# DMD_1_0.net
KiCad netlist of a schematic drawn in EAGLE
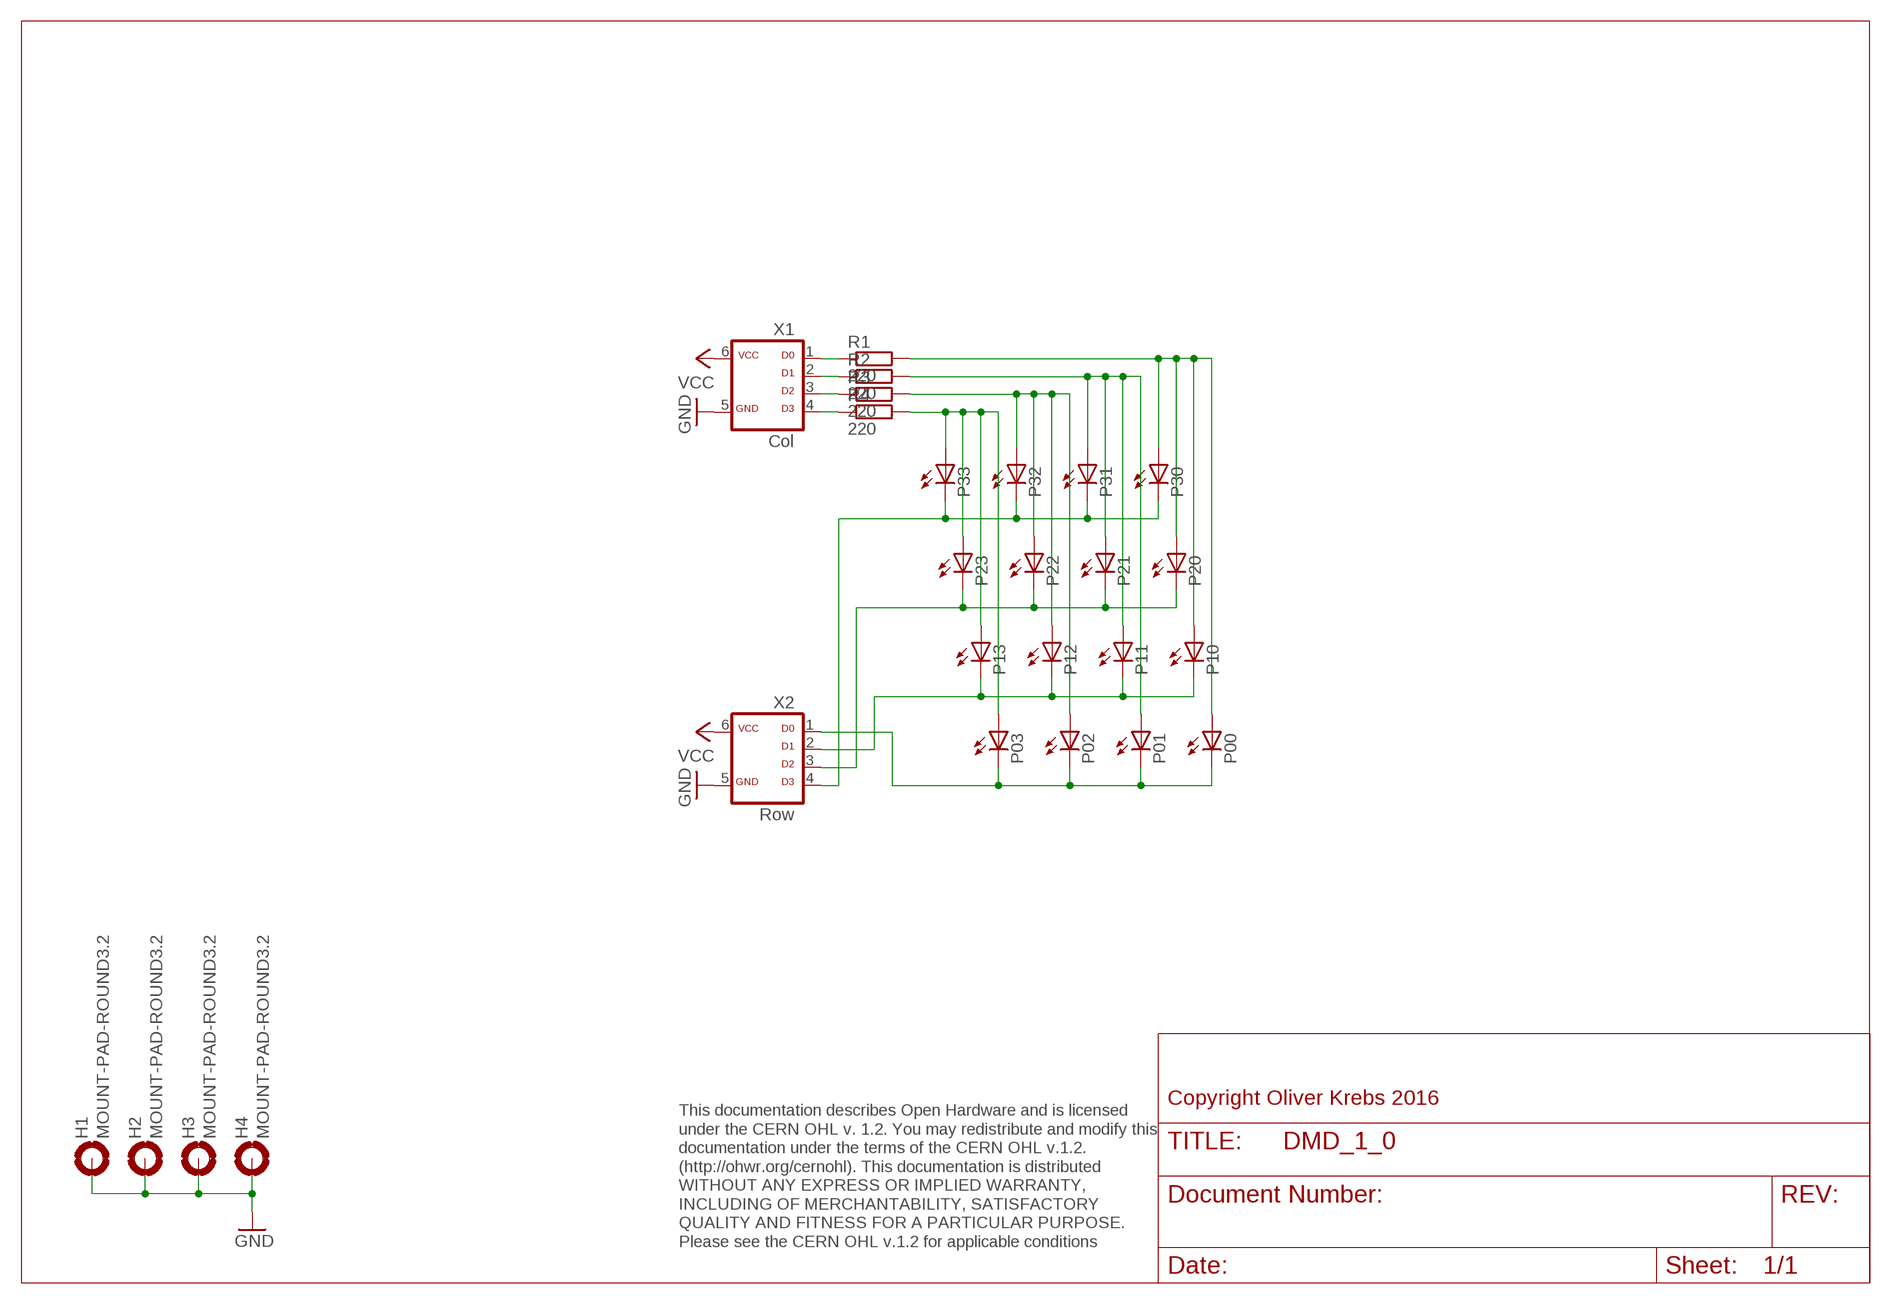
[diagram p0: schematic, sheet 1]

(export (version "E")
  (design (tool "Eeschema 10.0.6"))
  (components
    (comp (ref "H1")
      (value "MOUNT-PAD-ROUND3.2")
      (footprint "eagle-import:3,2-PAD")
      (libsource (lib "eagle-import") (part "MOUNT-PAD-ROUND3.2"))
    )
    (comp (ref "H2")
      (value "MOUNT-PAD-ROUND3.2")
      (footprint "eagle-import:3,2-PAD")
      (libsource (lib "eagle-import") (part "MOUNT-PAD-ROUND3.2"))
    )
    (comp (ref "H3")
      (value "MOUNT-PAD-ROUND3.2")
      (footprint "eagle-import:3,2-PAD")
      (libsource (lib "eagle-import") (part "MOUNT-PAD-ROUND3.2"))
    )
    (comp (ref "H4")
      (value "MOUNT-PAD-ROUND3.2")
      (footprint "eagle-import:3,2-PAD")
      (libsource (lib "eagle-import") (part "MOUNT-PAD-ROUND3.2"))
    )
    (comp (ref "P00")
      (value "LED5MM")
      (footprint "eagle-import:LED5MM")
      (libsource (lib "eagle-import") (part "LED5MM"))
    )
    (comp (ref "P01")
      (value "LED5MM")
      (footprint "eagle-import:LED5MM")
      (libsource (lib "eagle-import") (part "LED5MM"))
    )
    (comp (ref "P02")
      (value "LED5MM")
      (footprint "eagle-import:LED5MM")
      (libsource (lib "eagle-import") (part "LED5MM"))
    )
    (comp (ref "P03")
      (value "LED5MM")
      (footprint "eagle-import:LED5MM")
      (libsource (lib "eagle-import") (part "LED5MM"))
    )
    (comp (ref "P10")
      (value "LED5MM")
      (footprint "eagle-import:LED5MM")
      (libsource (lib "eagle-import") (part "LED5MM"))
    )
    (comp (ref "P11")
      (value "LED5MM")
      (footprint "eagle-import:LED5MM")
      (libsource (lib "eagle-import") (part "LED5MM"))
    )
    (comp (ref "P12")
      (value "LED5MM")
      (footprint "eagle-import:LED5MM")
      (libsource (lib "eagle-import") (part "LED5MM"))
    )
    (comp (ref "P13")
      (value "LED5MM")
      (footprint "eagle-import:LED5MM")
      (libsource (lib "eagle-import") (part "LED5MM"))
    )
    (comp (ref "P20")
      (value "LED5MM")
      (footprint "eagle-import:LED5MM")
      (libsource (lib "eagle-import") (part "LED5MM"))
    )
    (comp (ref "P21")
      (value "LED5MM")
      (footprint "eagle-import:LED5MM")
      (libsource (lib "eagle-import") (part "LED5MM"))
    )
    (comp (ref "P22")
      (value "LED5MM")
      (footprint "eagle-import:LED5MM")
      (libsource (lib "eagle-import") (part "LED5MM"))
    )
    (comp (ref "P23")
      (value "LED5MM")
      (footprint "eagle-import:LED5MM")
      (libsource (lib "eagle-import") (part "LED5MM"))
    )
    (comp (ref "P30")
      (value "LED5MM")
      (footprint "eagle-import:LED5MM")
      (libsource (lib "eagle-import") (part "LED5MM"))
    )
    (comp (ref "P31")
      (value "LED5MM")
      (footprint "eagle-import:LED5MM")
      (libsource (lib "eagle-import") (part "LED5MM"))
    )
    (comp (ref "P32")
      (value "LED5MM")
      (footprint "eagle-import:LED5MM")
      (libsource (lib "eagle-import") (part "LED5MM"))
    )
    (comp (ref "P33")
      (value "LED5MM")
      (footprint "eagle-import:LED5MM")
      (libsource (lib "eagle-import") (part "LED5MM"))
    )
    (comp (ref "R1")
      (value "220")
      (footprint "eagle-import:0207_10")
      (libsource (lib "eagle-import") (part "R-EU_0207/10"))
    )
    (comp (ref "R2")
      (value "220")
      (footprint "eagle-import:0207_10")
      (libsource (lib "eagle-import") (part "R-EU_0207/10"))
    )
    (comp (ref "R3")
      (value "220")
      (footprint "eagle-import:0207_10")
      (libsource (lib "eagle-import") (part "R-EU_0207/10"))
    )
    (comp (ref "R4")
      (value "220")
      (footprint "eagle-import:0207_10")
      (libsource (lib "eagle-import") (part "R-EU_0207/10"))
    )
    (comp (ref "X1")
      (value "Col")
      (footprint "eagle-import:ML-6")
      (libsource (lib "eagle-import") (part "ML6D"))
    )
    (comp (ref "X2")
      (value "Row")
      (footprint "eagle-import:ML-6")
      (libsource (lib "eagle-import") (part "ML6D"))
    )
  )
  (nets
    (net (code "1") (name "GND") (class "Default")
      (node (ref "H1") (pin "B3,2") (pinfunction "MOUNT_B3,2") (pintype "passive"))
      (node (ref "H2") (pin "B3,2") (pinfunction "MOUNT_B3,2") (pintype "passive"))
      (node (ref "H3") (pin "B3,2") (pinfunction "MOUNT_B3,2") (pintype "passive"))
      (node (ref "H4") (pin "B3,2") (pinfunction "MOUNT_B3,2") (pintype "passive"))
      (node (ref "X1") (pin "5") (pinfunction "5_5") (pintype "passive"))
      (node (ref "X2") (pin "5") (pinfunction "5_5") (pintype "passive"))
    )
    (net (code "2") (name "Net-(P00-C)") (class "Default")
      (node (ref "P00") (pin "K") (pinfunction "C_K") (pintype "passive"))
      (node (ref "P01") (pin "K") (pinfunction "C_K") (pintype "passive"))
      (node (ref "P02") (pin "K") (pinfunction "C_K") (pintype "passive"))
      (node (ref "P03") (pin "K") (pinfunction "C_K") (pintype "passive"))
      (node (ref "X2") (pin "1") (pinfunction "1_1") (pintype "passive"))
    )
    (net (code "3") (name "Net-(P00-PadA)") (class "Default")
      (node (ref "P00") (pin "A") (pinfunction "A_A") (pintype "passive"))
      (node (ref "P10") (pin "A") (pinfunction "A_A") (pintype "passive"))
      (node (ref "P20") (pin "A") (pinfunction "A_A") (pintype "passive"))
      (node (ref "P30") (pin "A") (pinfunction "A_A") (pintype "passive"))
      (node (ref "R1") (pin "2") (pinfunction "2_2") (pintype "passive"))
    )
    (net (code "4") (name "Net-(P01-PadA)") (class "Default")
      (node (ref "P01") (pin "A") (pinfunction "A_A") (pintype "passive"))
      (node (ref "P11") (pin "A") (pinfunction "A_A") (pintype "passive"))
      (node (ref "P21") (pin "A") (pinfunction "A_A") (pintype "passive"))
      (node (ref "P31") (pin "A") (pinfunction "A_A") (pintype "passive"))
      (node (ref "R2") (pin "2") (pinfunction "2_2") (pintype "passive"))
    )
    (net (code "5") (name "Net-(P02-PadA)") (class "Default")
      (node (ref "P02") (pin "A") (pinfunction "A_A") (pintype "passive"))
      (node (ref "P12") (pin "A") (pinfunction "A_A") (pintype "passive"))
      (node (ref "P22") (pin "A") (pinfunction "A_A") (pintype "passive"))
      (node (ref "P32") (pin "A") (pinfunction "A_A") (pintype "passive"))
      (node (ref "R3") (pin "2") (pinfunction "2_2") (pintype "passive"))
    )
    (net (code "6") (name "Net-(P03-PadA)") (class "Default")
      (node (ref "P03") (pin "A") (pinfunction "A_A") (pintype "passive"))
      (node (ref "P13") (pin "A") (pinfunction "A_A") (pintype "passive"))
      (node (ref "P23") (pin "A") (pinfunction "A_A") (pintype "passive"))
      (node (ref "P33") (pin "A") (pinfunction "A_A") (pintype "passive"))
      (node (ref "R4") (pin "2") (pinfunction "2_2") (pintype "passive"))
    )
    (net (code "7") (name "Net-(P10-C)") (class "Default")
      (node (ref "P10") (pin "K") (pinfunction "C_K") (pintype "passive"))
      (node (ref "P11") (pin "K") (pinfunction "C_K") (pintype "passive"))
      (node (ref "P12") (pin "K") (pinfunction "C_K") (pintype "passive"))
      (node (ref "P13") (pin "K") (pinfunction "C_K") (pintype "passive"))
      (node (ref "X2") (pin "2") (pinfunction "2_2") (pintype "passive"))
    )
    (net (code "8") (name "Net-(P20-C)") (class "Default")
      (node (ref "P20") (pin "K") (pinfunction "C_K") (pintype "passive"))
      (node (ref "P21") (pin "K") (pinfunction "C_K") (pintype "passive"))
      (node (ref "P22") (pin "K") (pinfunction "C_K") (pintype "passive"))
      (node (ref "P23") (pin "K") (pinfunction "C_K") (pintype "passive"))
      (node (ref "X2") (pin "3") (pinfunction "3_3") (pintype "passive"))
    )
    (net (code "9") (name "Net-(P30-C)") (class "Default")
      (node (ref "P30") (pin "K") (pinfunction "C_K") (pintype "passive"))
      (node (ref "P31") (pin "K") (pinfunction "C_K") (pintype "passive"))
      (node (ref "P32") (pin "K") (pinfunction "C_K") (pintype "passive"))
      (node (ref "P33") (pin "K") (pinfunction "C_K") (pintype "passive"))
      (node (ref "X2") (pin "4") (pinfunction "4_4") (pintype "passive"))
    )
    (net (code "10") (name "Net-(R1-Pad1)") (class "Default")
      (node (ref "R1") (pin "1") (pinfunction "1_1") (pintype "passive"))
      (node (ref "X1") (pin "1") (pinfunction "1_1") (pintype "passive"))
    )
    (net (code "11") (name "Net-(R2-Pad1)") (class "Default")
      (node (ref "R2") (pin "1") (pinfunction "1_1") (pintype "passive"))
      (node (ref "X1") (pin "2") (pinfunction "2_2") (pintype "passive"))
    )
    (net (code "12") (name "Net-(R3-Pad1)") (class "Default")
      (node (ref "R3") (pin "1") (pinfunction "1_1") (pintype "passive"))
      (node (ref "X1") (pin "3") (pinfunction "3_3") (pintype "passive"))
    )
    (net (code "13") (name "Net-(R4-Pad1)") (class "Default")
      (node (ref "R4") (pin "1") (pinfunction "1_1") (pintype "passive"))
      (node (ref "X1") (pin "4") (pinfunction "4_4") (pintype "passive"))
    )
    (net (code "14") (name "VCC") (class "Default")
      (node (ref "X1") (pin "6") (pinfunction "6_6") (pintype "passive"))
      (node (ref "X2") (pin "6") (pinfunction "6_6") (pintype "passive"))
    )
  )
)
